# 2__Power.net
KiCad netlist of a schematic drawn in Altium Designer
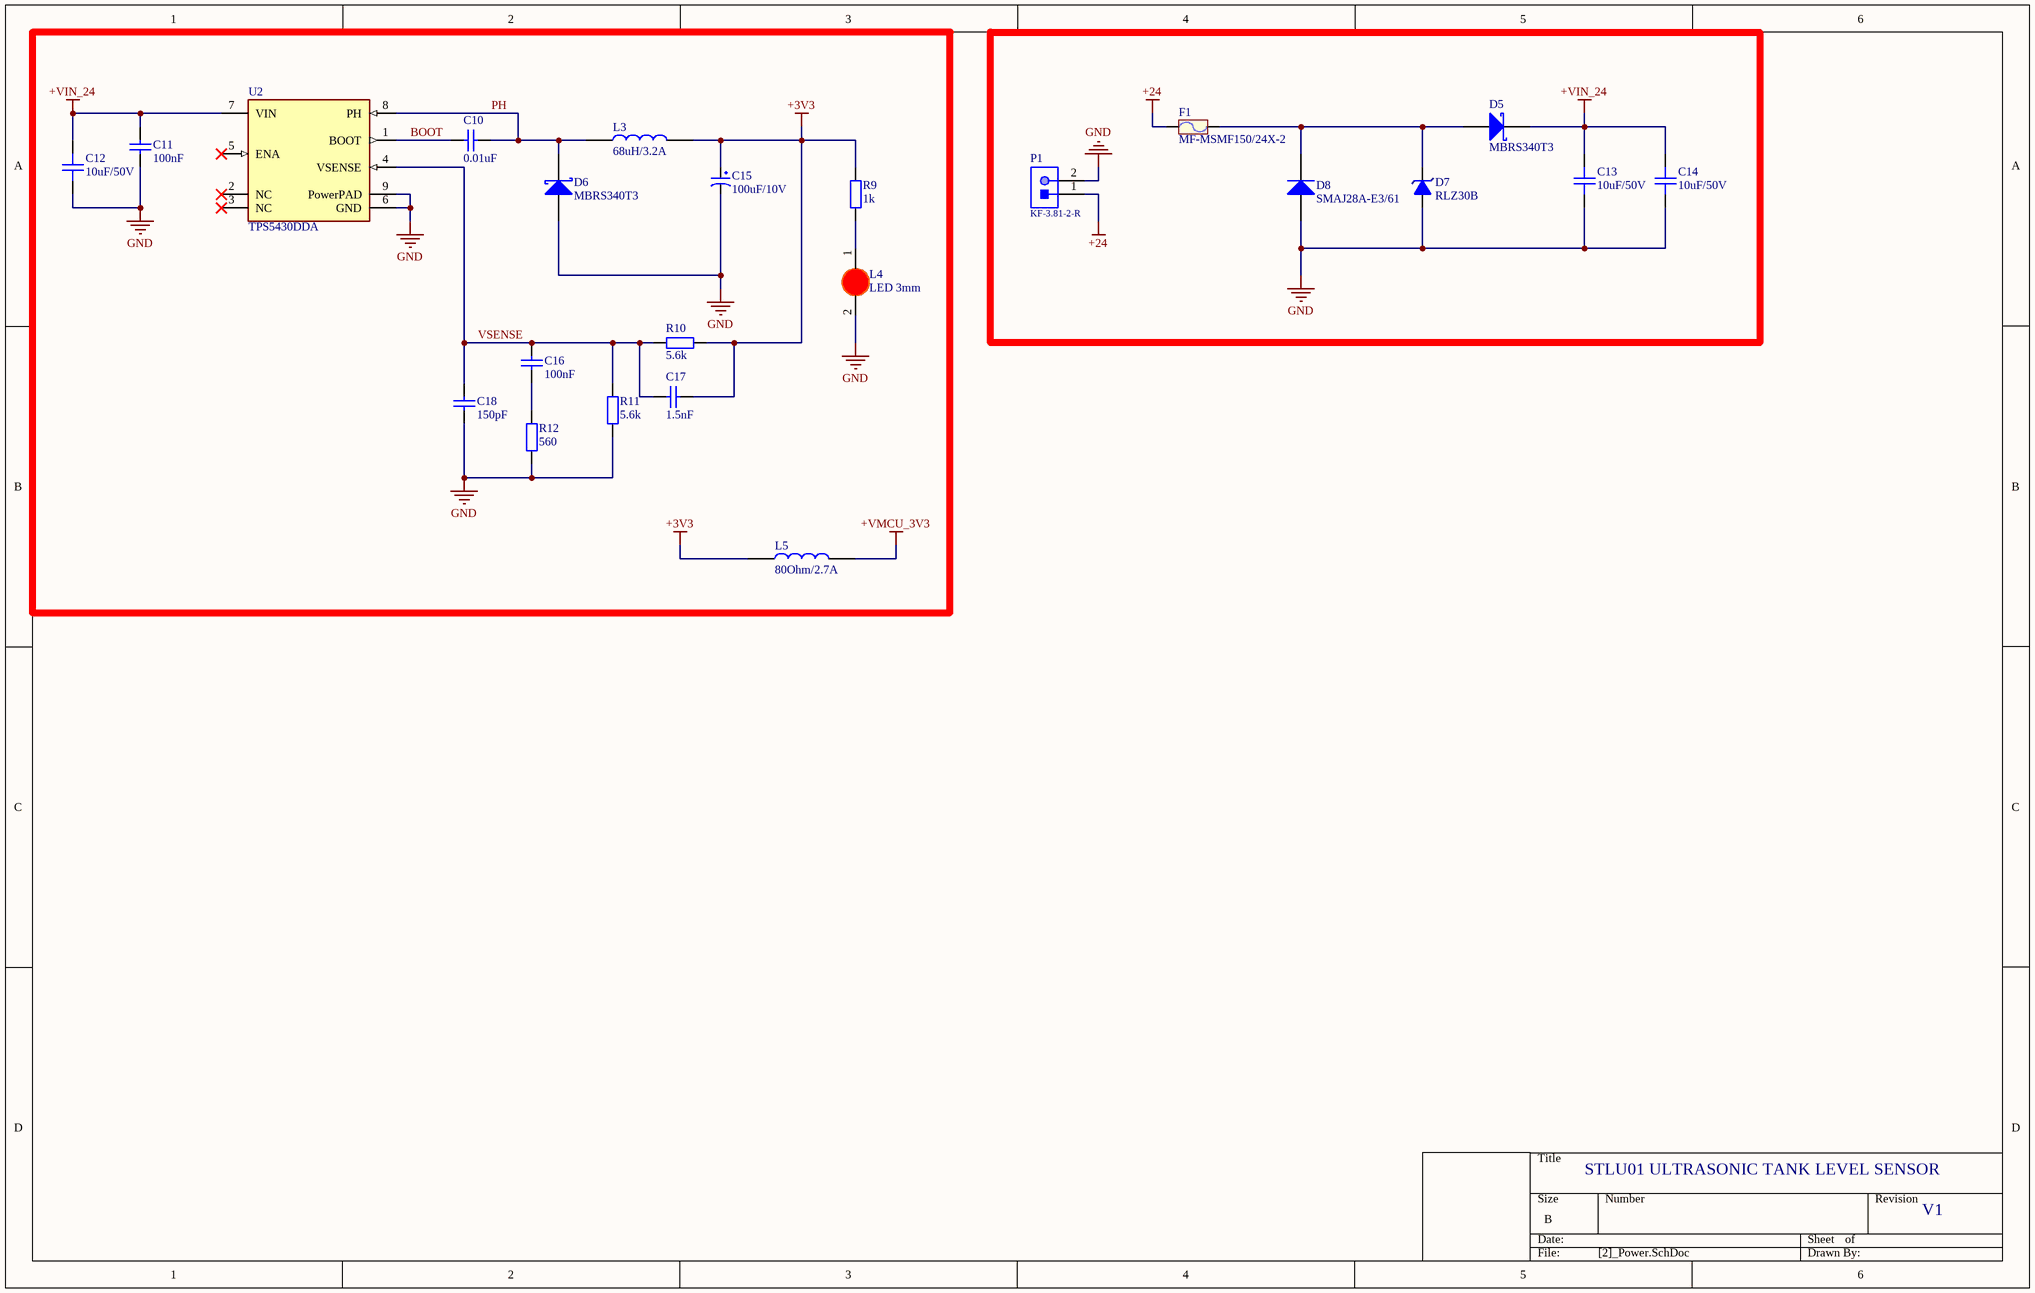
[diagram p0: [2]_Power.SchDoc]

(export (version "E")
  (design (tool "Eeschema 10.0.6"))
  (components
    (comp (ref "C10")
      (value "0.01uF")
      (footprint "tu 0603")
      (description "Dán")
      (libsource (lib "Altium_Lib_by_KhueNguyenCreator") (part "Tu 0603 105 16V 20%"))
    )
    (comp (ref "C11")
      (value "100nF")
      (footprint "tu 0805")
      (description "Dán")
      (libsource (lib "Altium_Lib_by_KhueNguyenCreator") (part "Tu 0805 10pF 50V 10%"))
    )
    (comp (ref "C12")
      (value "10uF/50V")
      (footprint "1210")
      (description "CAP CER 10uF/50V 1210")
      (fields (field (name "MANUFACTURER") "Yageo") (field (name "PART NUMBER") "C1210"))
      (libsource (lib "COMPONENT_INS") (part "CAP_CER_1210_10uF"))
    )
    (comp (ref "C13")
      (value "10uF/50V")
      (footprint "1210")
      (description "CAP CER 10uF/50V 1210")
      (fields (field (name "MANUFACTURER") "Yageo") (field (name "PART NUMBER") "C1210"))
      (libsource (lib "COMPONENT_INS") (part "CAP_CER_1210_10uF"))
    )
    (comp (ref "C14")
      (value "10uF/50V")
      (footprint "1210")
      (description "CAP CER 10uF/50V 1210")
      (fields (field (name "MANUFACTURER") "Yageo") (field (name "PART NUMBER") "C1210"))
      (libsource (lib "COMPONENT_INS") (part "CAP_CER_1210_10uF"))
    )
    (comp (ref "C15")
      (value "100uF/10V")
      (footprint "2312")
      (description "CAP TANT 100uF/10V 2312")
      (fields (field (name "MANUFACTURER") "AVX") (field (name "PART NUMBER") "TAJC107K010RNJ"))
      (libsource (lib "COMPONENT_INS") (part "CAP_TANT_2312_100uF"))
    )
    (comp (ref "C16")
      (value "100nF")
      (footprint "tu 0805")
      (description "Dán")
      (libsource (lib "Altium_Lib_by_KhueNguyenCreator") (part "Tu 0805 10pF 50V 10%"))
    )
    (comp (ref "C17")
      (value "1.5nF")
      (footprint "tu 0805")
      (description "Dán")
      (libsource (lib "Altium_Lib_by_KhueNguyenCreator") (part "Tu 0805 10pF 50V 10%"))
    )
    (comp (ref "C18")
      (value "150pF")
      (footprint "tu 0805")
      (description "Dán")
      (libsource (lib "Altium_Lib_by_KhueNguyenCreator") (part "Tu 0805 10pF 50V 10%"))
    )
    (comp (ref "D5")
      (value "MBRS340T3")
      (footprint "DO214AB_SMC")
      (description "DIODE SCHOTTKY 4A 40V SMC DO-214AB")
      (fields (field (name "MANUFACTURER") "Fairchild") (field (name "PART NUMBER") "SS14"))
      (libsource (lib "COMPONENT_INS") (part "DIO_MBRS340T3"))
    )
    (comp (ref "D6")
      (value "MBRS340T3")
      (footprint "DO214AB_SMC")
      (description "DIODE SCHOTTKY 4A 40V SMC DO-214AB")
      (fields (field (name "MANUFACTURER") "Fairchild") (field (name "PART NUMBER") "SS14"))
      (libsource (lib "COMPONENT_INS") (part "DIO_MBRS340T3"))
    )
    (comp (ref "D7")
      (value "RLZ30B")
      (footprint "SOD_80")
      (description "ZMM15 15V 500mW SMD SOD-80")
      (fields (field (name "MANUFACTURER") "On Semiconductor") (field (name "PART NUMBER") "ZMM15"))
      (libsource (lib "COMPONENT_INS") (part "DIO_ZMM15"))
    )
    (comp (ref "D8")
      (value "SMAJ28A-E3/61")
      (footprint "VISH-DO-214AC-2_L")
      (fields (field (name "MANUFACTURER") "Vishay Semiconductor"))
      (libsource (lib "Altium Content Vault") (part "VISH-K1A2-2"))
    )
    (comp (ref "F1")
      (value "MF-MSMF150/24X-2")
      (footprint "1812")
      (description "MF-MSMF250/16 16V 2.5A1812")
      (fields (field (name "MANUFACTURER") "Bourns") (field (name "PART NUMBER") "1812"))
      (libsource (lib "COMPONENT_INS") (part "FUSE_16V_2.5A"))
    )
    (comp (ref "L3")
      (value "68uH/3.2A")
      (footprint "IND-12_12_8")
      (description "CDRH127 IND 68uH 3.2A 12x12x8")
      (fields (field (name "MANUFACTURER") "OEM") (field (name "PART NUMBER") "CDRH127"))
      (libsource (lib "COMPONENT_INS") (part "IND_68uH_3.2A_1280"))
    )
    (comp (ref "L4")
      (value "LED 3mm")
      (footprint "LED-3MM-RED")
      (description "Cắm")
      (libsource (lib "Altium_Lib_by_KhueNguyenCreator") (part "LED 3mm Do"))
    )
    (comp (ref "L5")
      (value "80Ohm/2.7A")
      (footprint "FER-0805 (2012)")
      (description "FERRITE BEAD 2.7A 80 OHM 0805")
      (fields (field (name "MANUFACTURER") "Taiyo Yuden") (field (name "PART NUMBER") "FBMH2012HM800-T"))
      (libsource (lib "COMPONENT_INS") (part "FERRITE_BEAD_2.7A_80"))
    )
    (comp (ref "P1")
      (value "KF-3.81-2-R")
      (footprint "691322310002")
      (description "Serie 322 - 3.81mm Horizontal PCB Header WR-TBL, 2 pin")
      (fields
        (field (name "PART NUMBER") "691322310002")
        (field (name "MANUFACTURER") "Wurth Elektronik")
        (field (name "PUBLISHER") "WurthElektronik")
      )
      (libsource (lib "Altium Content Vault") (part "WE-CN-1P-M-R2"))
    )
    (comp (ref "R9")
      (value "1k")
      (footprint "tro smd 0805")
      (description "Dán")
      (libsource (lib "Altium_Lib_by_KhueNguyenCreator") (part "Tro 0805 1% 5.1k"))
    )
    (comp (ref "R10")
      (value "5.6k")
      (footprint "tro smd 0805")
      (description "Dán")
      (libsource (lib "Altium_Lib_by_KhueNguyenCreator") (part "Tro 0805 1% 5.1k"))
    )
    (comp (ref "R11")
      (value "5.6k")
      (footprint "tro smd 0805")
      (description "Dán")
      (libsource (lib "Altium_Lib_by_KhueNguyenCreator") (part "Tro 0805 1% 5.1k"))
    )
    (comp (ref "R12")
      (value "560")
      (footprint "tro smd 0805")
      (description "Dán")
      (libsource (lib "Altium_Lib_by_KhueNguyenCreator") (part "Tro 0805 1% 5.1k"))
    )
    (comp (ref "U2")
      (value "TPS5430DDA")
      (footprint "FP-DDA0008J-MFG")
      (description "IC REG BUCK ADJUSTABLE 3A 8SOPWR")
      (fields
        (field (name "MANUFACTURER") "Texas Instruments")
        (field (name "OCTOPART") "https://octopart.com/tps5430dda-texas+instruments-589977")
      )
      (libsource (lib "Altium Content Vault") (part "98da629940cea6febc5630bb55159f3"))
    )
  )
  (nets
    (net (code "1") (name "+3V3") (class "Default")
      (node (ref "C15") (pin "1") (pinfunction "1_1") (pintype "passive"))
      (node (ref "C17") (pin "2") (pinfunction "2_2") (pintype "passive"))
      (node (ref "L3") (pin "2") (pinfunction "2_2") (pintype "passive"))
      (node (ref "L5") (pin "1") (pinfunction "1_1") (pintype "passive"))
      (node (ref "R10") (pin "1") (pinfunction "1_1") (pintype "passive"))
      (node (ref "R9") (pin "2") (pinfunction "2_2") (pintype "passive"))
    )
    (net (code "2") (name "+24") (class "Default")
      (node (ref "F1") (pin "1") (pinfunction "1_1") (pintype "passive"))
      (node (ref "P1") (pin "1") (pinfunction "1_1") (pintype "passive"))
    )
    (net (code "3") (name "+VIN_24") (class "Default")
      (node (ref "C11") (pin "1") (pinfunction "1_1") (pintype "passive"))
      (node (ref "C12") (pin "2") (pinfunction "2_2") (pintype "passive"))
      (node (ref "C13") (pin "2") (pinfunction "2_2") (pintype "passive"))
      (node (ref "C14") (pin "2") (pinfunction "2_2") (pintype "passive"))
      (node (ref "D5") (pin "2") (pinfunction "K_2") (pintype "passive"))
      (node (ref "U2") (pin "7") (pinfunction "VIN_7") (pintype "power_in"))
    )
    (net (code "4") (name "+VMCU_3V3") (class "Default")
      (node (ref "L5") (pin "2") (pinfunction "2_2") (pintype "passive"))
    )
    (net (code "5") (name "/BOOT") (class "Default")
      (node (ref "C10") (pin "2") (pinfunction "2_2") (pintype "passive"))
      (node (ref "U2") (pin "1") (pinfunction "BOOT_1") (pintype "output"))
    )
    (net (code "6") (name "/PH") (class "Default")
      (node (ref "C10") (pin "1") (pinfunction "1_1") (pintype "passive"))
      (node (ref "D6") (pin "2") (pinfunction "K_2") (pintype "passive"))
      (node (ref "L3") (pin "1") (pinfunction "1_1") (pintype "passive"))
      (node (ref "U2") (pin "8") (pinfunction "PH_8") (pintype "input"))
    )
    (net (code "7") (name "/VSENSE") (class "Default")
      (node (ref "C16") (pin "1") (pinfunction "1_1") (pintype "passive"))
      (node (ref "C17") (pin "1") (pinfunction "1_1") (pintype "passive"))
      (node (ref "C18") (pin "1") (pinfunction "1_1") (pintype "passive"))
      (node (ref "R10") (pin "2") (pinfunction "2_2") (pintype "passive"))
      (node (ref "R11") (pin "2") (pinfunction "2_2") (pintype "passive"))
      (node (ref "U2") (pin "4") (pinfunction "VSENSE_4") (pintype "input"))
    )
    (net (code "8") (name "GND") (class "Default")
      (node (ref "C11") (pin "2") (pinfunction "2_2") (pintype "passive"))
      (node (ref "C12") (pin "1") (pinfunction "1_1") (pintype "passive"))
      (node (ref "C13") (pin "1") (pinfunction "1_1") (pintype "passive"))
      (node (ref "C14") (pin "1") (pinfunction "1_1") (pintype "passive"))
      (node (ref "C15") (pin "2") (pinfunction "2_2") (pintype "passive"))
      (node (ref "C18") (pin "2") (pinfunction "2_2") (pintype "passive"))
      (node (ref "D6") (pin "1") (pinfunction "A_1") (pintype "passive"))
      (node (ref "D7") (pin "1") (pinfunction "A_1") (pintype "passive"))
      (node (ref "D8") (pin "2") (pinfunction "A_2") (pintype "passive"))
      (node (ref "L4") (pin "2") (pinfunction "K_2") (pintype "passive"))
      (node (ref "P1") (pin "2") (pinfunction "2_2") (pintype "passive"))
      (node (ref "R11") (pin "1") (pinfunction "1_1") (pintype "passive"))
      (node (ref "R12") (pin "1") (pinfunction "1_1") (pintype "passive"))
      (node (ref "U2") (pin "6") (pinfunction "GND_6") (pintype "power_in"))
      (node (ref "U2") (pin "9") (pinfunction "PowerPAD_9") (pintype "power_in"))
    )
    (net (code "9") (name "Net-(C16-Pad2)") (class "Default")
      (node (ref "C16") (pin "2") (pinfunction "2_2") (pintype "passive"))
      (node (ref "R12") (pin "2") (pinfunction "2_2") (pintype "passive"))
    )
    (net (code "10") (name "Net-(D5-A)") (class "Default")
      (node (ref "D5") (pin "1") (pinfunction "A_1") (pintype "passive"))
      (node (ref "D7") (pin "2") (pinfunction "K_2") (pintype "passive"))
      (node (ref "D8") (pin "1") (pinfunction "K_1") (pintype "passive"))
      (node (ref "F1") (pin "2") (pinfunction "2_2") (pintype "passive"))
    )
    (net (code "11") (name "Net-(L4-A)") (class "Default")
      (node (ref "L4") (pin "1") (pinfunction "A_1") (pintype "passive"))
      (node (ref "R9") (pin "1") (pinfunction "1_1") (pintype "passive"))
    )
    (net (code "12") (name "unconnected-(U2-ENA-Pad5)") (class "Default")
      (node (ref "U2") (pin "5") (pinfunction "ENA_5") (pintype "input+no_connect"))
    )
    (net (code "13") (name "unconnected-(U2-NC-Pad2)") (class "Default")
      (node (ref "U2") (pin "2") (pinfunction "NC_2") (pintype "passive+no_connect"))
    )
    (net (code "14") (name "unconnected-(U2-NC-Pad3)") (class "Default")
      (node (ref "U2") (pin "3") (pinfunction "NC_3") (pintype "passive+no_connect"))
    )
  )
)
